# zeta2rework_lw_v15.net
KiCad netlist of a schematic drawn in EAGLE
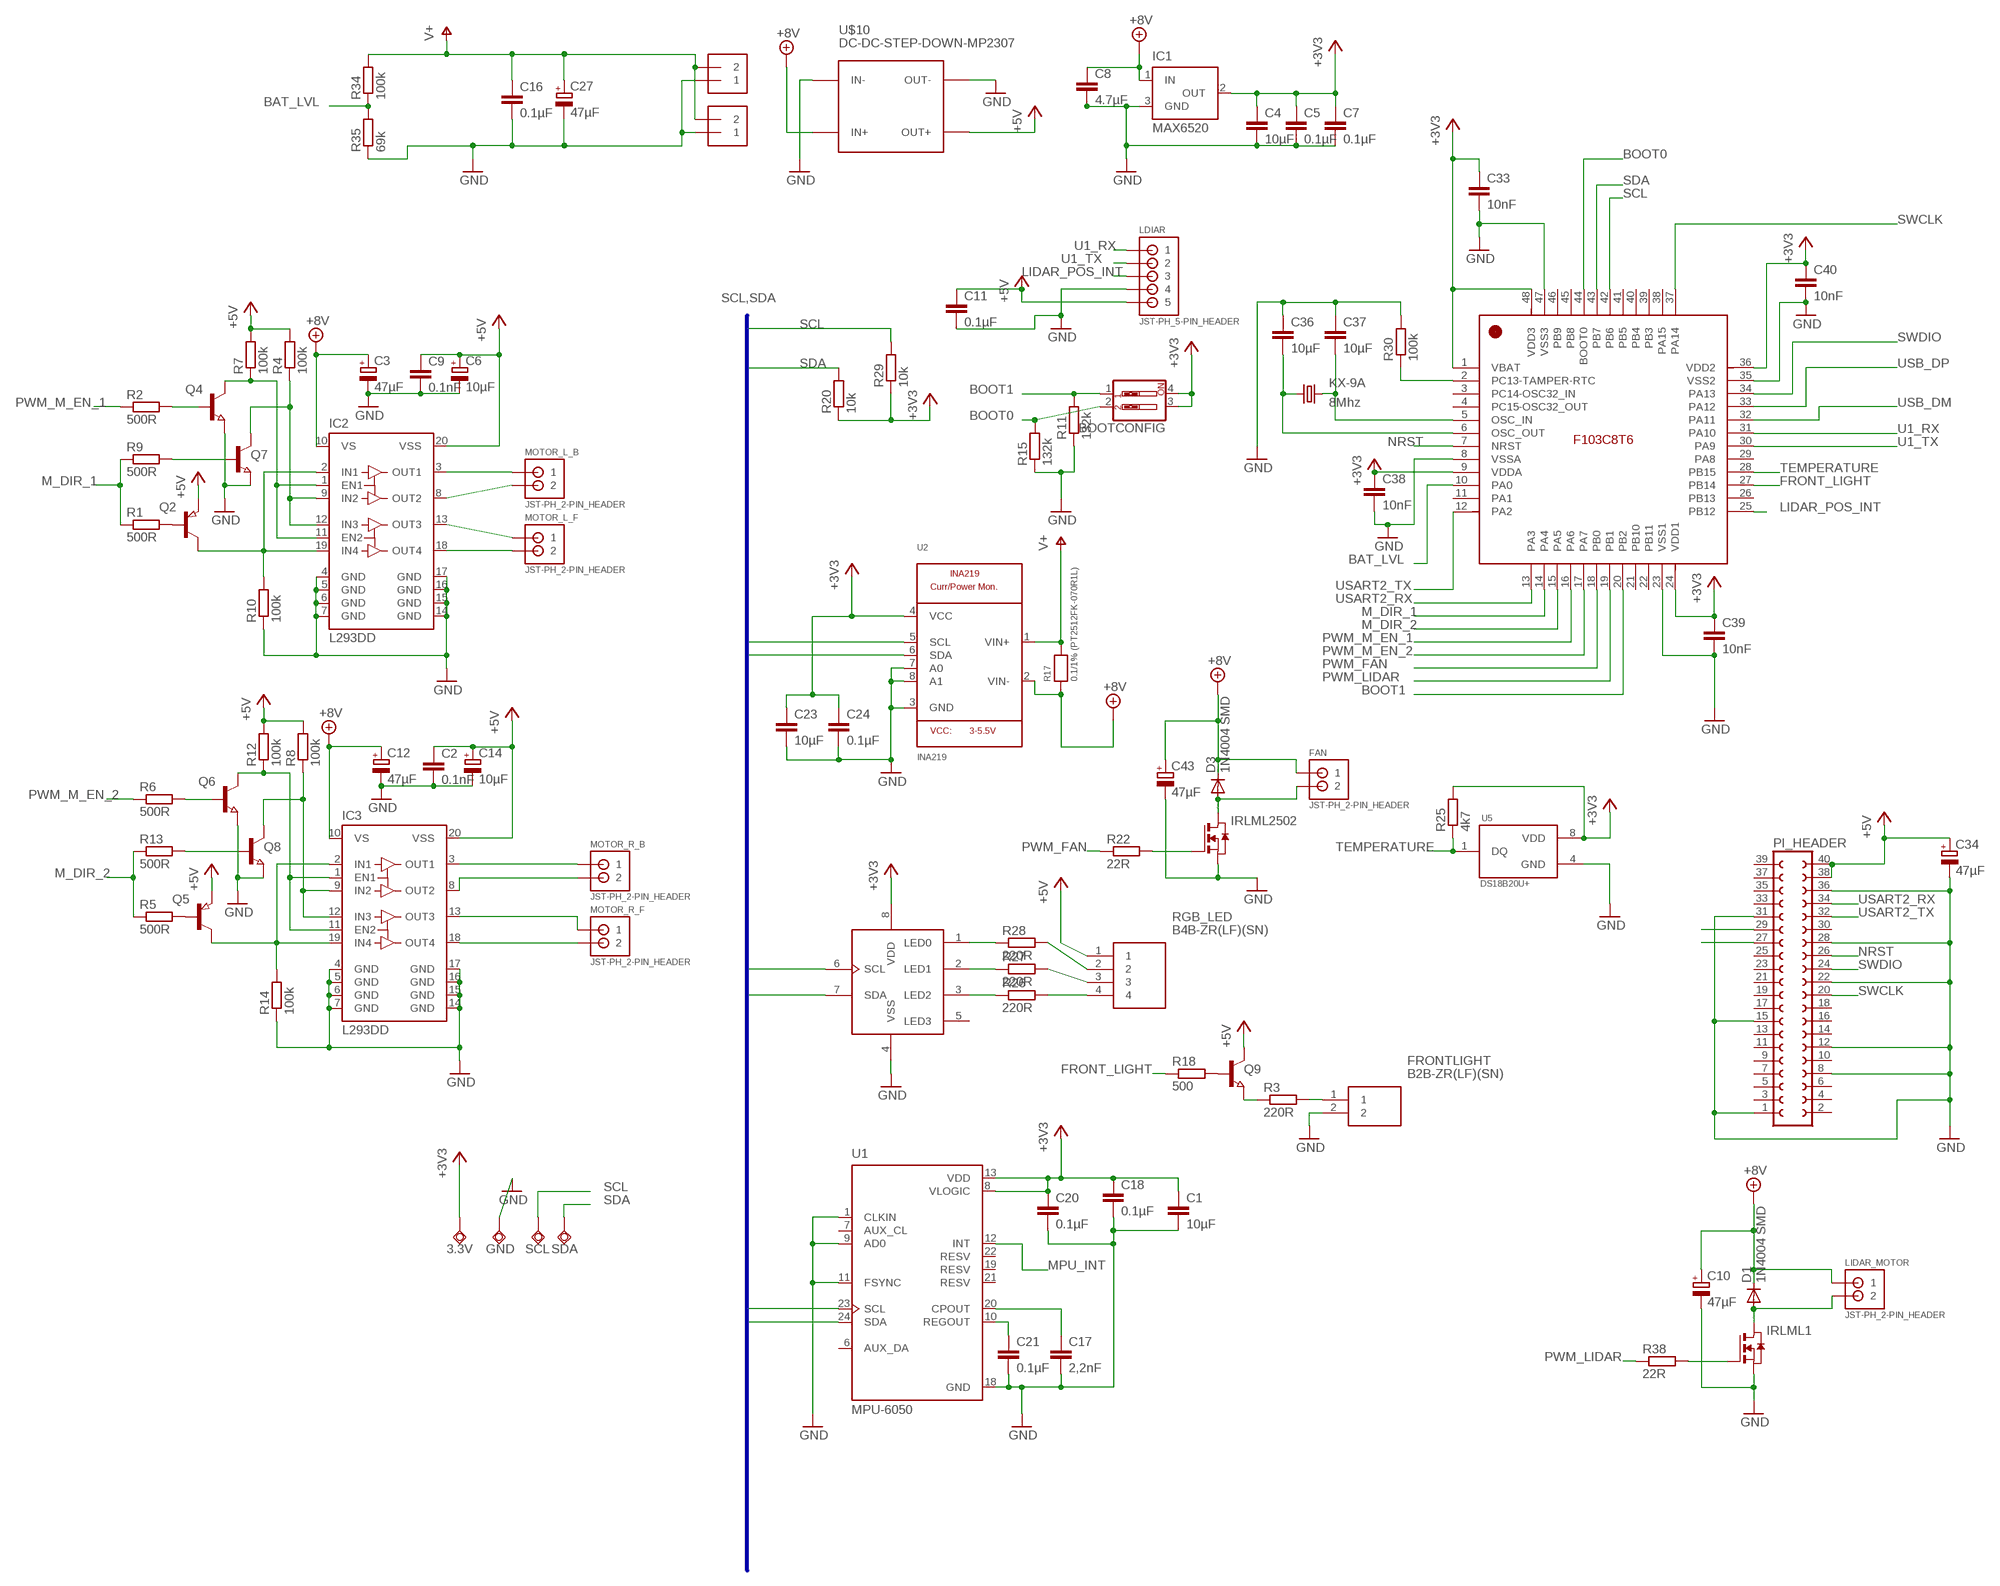
[diagram p0: schematic, sheet 1]

(export (version "E")
  (design (tool "Eeschema 10.0.6"))
  (components
    (comp (ref "3.3V")
      (value "TPSQTP20R")
      (footprint "eagle-import:TP20R")
      (libsource (lib "eagle-import") (part "TPSQTP20R"))
    )
    (comp (ref "BOOTCONFIG")
      (value "SW_DIP-2")
      (footprint "eagle-import:EDG-02")
      (libsource (lib "eagle-import") (part "SW_DIP-2"))
    )
    (comp (ref "C1")
      (value "10µF")
      (footprint "eagle-import:C1206")
      (libsource (lib "eagle-import") (part "C-EUC1206"))
    )
    (comp (ref "C2")
      (value "0.1nF")
      (footprint "eagle-import:C1206")
      (libsource (lib "eagle-import") (part "C-EUC1206"))
    )
    (comp (ref "C3")
      (value "47µF")
      (footprint "eagle-import:UD-4X5,8_NICHICON")
      (libsource (lib "eagle-import") (part "CPOL-EUUD-4X5,8"))
    )
    (comp (ref "C4")
      (value "10µF")
      (footprint "eagle-import:C1206")
      (libsource (lib "eagle-import") (part "C-EUC1206"))
    )
    (comp (ref "C5")
      (value "0.1µF")
      (footprint "eagle-import:C1206")
      (libsource (lib "eagle-import") (part "C-EUC1206"))
    )
    (comp (ref "C6")
      (value "10µF")
      (footprint "eagle-import:UD-4X5,8_NICHICON")
      (libsource (lib "eagle-import") (part "CPOL-EUUD-4X5,8"))
    )
    (comp (ref "C7")
      (value "0.1µF")
      (footprint "eagle-import:C1206")
      (libsource (lib "eagle-import") (part "C-EUC1206"))
    )
    (comp (ref "C8")
      (value "4.7µF")
      (footprint "eagle-import:C1206")
      (libsource (lib "eagle-import") (part "C-EUC1206"))
    )
    (comp (ref "C9")
      (value "0.1nF")
      (footprint "eagle-import:C1206")
      (libsource (lib "eagle-import") (part "C-EUC1206"))
    )
    (comp (ref "C10")
      (value "47µF")
      (footprint "eagle-import:UD-4X5,8_NICHICON")
      (libsource (lib "eagle-import") (part "CPOL-EUUD-4X5,8"))
    )
    (comp (ref "C11")
      (value "0.1µF")
      (footprint "eagle-import:C1206")
      (libsource (lib "eagle-import") (part "C-EUC1206"))
    )
    (comp (ref "C12")
      (value "47µF")
      (footprint "eagle-import:UD-4X5,8_NICHICON")
      (libsource (lib "eagle-import") (part "CPOL-EUUD-4X5,8"))
    )
    (comp (ref "C14")
      (value "10µF")
      (footprint "eagle-import:UD-4X5,8_NICHICON")
      (libsource (lib "eagle-import") (part "CPOL-EUUD-4X5,8"))
    )
    (comp (ref "C16")
      (value "0.1µF")
      (footprint "eagle-import:C1206")
      (libsource (lib "eagle-import") (part "C-EUC1206"))
    )
    (comp (ref "C17")
      (value "2,2nF")
      (footprint "eagle-import:C1206")
      (libsource (lib "eagle-import") (part "C-EUC1206"))
    )
    (comp (ref "C18")
      (value "0.1µF")
      (footprint "eagle-import:C1206")
      (libsource (lib "eagle-import") (part "C-EUC1206"))
    )
    (comp (ref "C20")
      (value "0.1µF")
      (footprint "eagle-import:C1206")
      (libsource (lib "eagle-import") (part "C-EUC1206"))
    )
    (comp (ref "C21")
      (value "0.1µF")
      (footprint "eagle-import:C1206")
      (libsource (lib "eagle-import") (part "C-EUC1206"))
    )
    (comp (ref "C23")
      (value "10µF")
      (footprint "eagle-import:C1206")
      (libsource (lib "eagle-import") (part "C-EUC1206"))
    )
    (comp (ref "C24")
      (value "0.1µF")
      (footprint "eagle-import:C1206")
      (libsource (lib "eagle-import") (part "C-EUC1206"))
    )
    (comp (ref "C27")
      (value "47µF")
      (footprint "eagle-import:UD-4X5,8_NICHICON")
      (libsource (lib "eagle-import") (part "CPOL-EUUD-4X5,8"))
    )
    (comp (ref "C33")
      (value "10nF")
      (footprint "eagle-import:C1206")
      (libsource (lib "eagle-import") (part "C-EUC1206"))
    )
    (comp (ref "C34")
      (value "47µF")
      (footprint "eagle-import:UD-4X5,8_NICHICON")
      (libsource (lib "eagle-import") (part "CPOL-EUUD-4X5,8"))
    )
    (comp (ref "C36")
      (value "10µF")
      (footprint "eagle-import:C1206")
      (libsource (lib "eagle-import") (part "C-EUC1206"))
    )
    (comp (ref "C37")
      (value "10µF")
      (footprint "eagle-import:C1206")
      (libsource (lib "eagle-import") (part "C-EUC1206"))
    )
    (comp (ref "C38")
      (value "10nF")
      (footprint "eagle-import:C1206")
      (libsource (lib "eagle-import") (part "C-EUC1206"))
    )
    (comp (ref "C39")
      (value "10nF")
      (footprint "eagle-import:C1206")
      (libsource (lib "eagle-import") (part "C-EUC1206"))
    )
    (comp (ref "C40")
      (value "10nF")
      (footprint "eagle-import:C1206")
      (libsource (lib "eagle-import") (part "C-EUC1206"))
    )
    (comp (ref "C43")
      (value "47µF")
      (footprint "eagle-import:UD-4X5,8_NICHICON")
      (libsource (lib "eagle-import") (part "CPOL-EUUD-4X5,8"))
    )
    (comp (ref "D1")
      (value "1N4004 SMD")
      (footprint "eagle-import:DO214AC")
      (libsource (lib "eagle-import") (part "DIODE-DO214AC"))
    )
    (comp (ref "D3")
      (value "1N4004 SMD")
      (footprint "eagle-import:DO214AC")
      (libsource (lib "eagle-import") (part "DIODE-DO214AC"))
    )
    (comp (ref "FAN")
      (value "JST-PH_2-PIN_HEADER")
      (footprint "eagle-import:JST_B2B-PH_HEADER")
      (libsource (lib "eagle-import") (part "JST-PH_2-PIN_HEADER"))
    )
    (comp (ref "FRONTLIGHT")
      (value "B2B-ZR(LF)(SN)")
      (footprint "eagle-import:SHDR2W50P0X150_1X2_450X350X450")
      (fields (field (name "MOUSER_PART_NUMBER") "1724868"))
      (libsource (lib "eagle-import") (part "B2B-ZR(LF)(SN)"))
    )
    (comp (ref "GND")
      (value "TPSQTP20R")
      (footprint "eagle-import:TP20R")
      (libsource (lib "eagle-import") (part "TPSQTP20R"))
    )
    (comp (ref "IC1")
      (value "MAX6520")
      (footprint "eagle-import:SOT23")
      (fields (field (name "MF") "MAXIM") (field (name "MPN") "MAX6520EUR-T"))
      (libsource (lib "eagle-import") (part "MAX6520"))
    )
    (comp (ref "IC2")
      (value "L293DD")
      (footprint "eagle-import:SO20")
      (libsource (lib "eagle-import") (part "L293DD"))
    )
    (comp (ref "IC3")
      (value "L293DD")
      (footprint "eagle-import:SO20")
      (libsource (lib "eagle-import") (part "L293DD"))
    )
    (comp (ref "IRLML1")
      (value "NMOSSOT23")
      (footprint "eagle-import:SOT-23")
      (libsource (lib "eagle-import") (part "NMOSSOT23"))
    )
    (comp (ref "IRLML2502")
      (value "NMOSSOT23")
      (footprint "eagle-import:SOT-23")
      (libsource (lib "eagle-import") (part "NMOSSOT23"))
    )
    (comp (ref "KX-9A")
      (value "8Mhz")
      (footprint "eagle-import:5.0X3.2_KX-9A")
      (libsource (lib "eagle-import") (part "KX-9A"))
    )
    (comp (ref "LDIAR")
      (value "JST-PH_5-PIN_HEADER")
      (footprint "eagle-import:JST_B5B-PH_HEADER")
      (libsource (lib "eagle-import") (part "JST-PH_5-PIN_HEADER"))
    )
    (comp (ref "LIDAR_MOTOR")
      (value "JST-PH_2-PIN_HEADER")
      (footprint "eagle-import:JST_B2B-PH_HEADER")
      (libsource (lib "eagle-import") (part "JST-PH_2-PIN_HEADER"))
    )
    (comp (ref "MOTOR_L_B")
      (value "JST-PH_2-PIN_HEADER")
      (footprint "eagle-import:JST_B2B-PH_HEADER")
      (libsource (lib "eagle-import") (part "JST-PH_2-PIN_HEADER"))
    )
    (comp (ref "MOTOR_L_F")
      (value "JST-PH_2-PIN_HEADER")
      (footprint "eagle-import:JST_B2B-PH_HEADER")
      (libsource (lib "eagle-import") (part "JST-PH_2-PIN_HEADER"))
    )
    (comp (ref "MOTOR_R_B")
      (value "JST-PH_2-PIN_HEADER")
      (footprint "eagle-import:JST_B2B-PH_HEADER")
      (libsource (lib "eagle-import") (part "JST-PH_2-PIN_HEADER"))
    )
    (comp (ref "MOTOR_R_F")
      (value "JST-PH_2-PIN_HEADER")
      (footprint "eagle-import:JST_B2B-PH_HEADER")
      (libsource (lib "eagle-import") (part "JST-PH_2-PIN_HEADER"))
    )
    (comp (ref "PCA9533")
      (value "PCA9533")
      (footprint "eagle-import:SOIC8")
      (libsource (lib "eagle-import") (part "PCA9533"))
    )
    (comp (ref "PI_HEADER")
      (value "FE20-2")
      (footprint "eagle-import:FE20-2")
      (libsource (lib "eagle-import") (part "FE20-2"))
    )
    (comp (ref "Q2")
      (value "PNP-TRANSISTOR_SOT23")
      (footprint "eagle-import:SOT23")
      (libsource (lib "eagle-import") (part "PNP-TRANSISTOR_SOT23"))
    )
    (comp (ref "Q4")
      (value "NPN-TRANSISTOR_SOT23")
      (footprint "eagle-import:SOT23")
      (libsource (lib "eagle-import") (part "NPN-TRANSISTOR_SOT23"))
    )
    (comp (ref "Q5")
      (value "PNP-TRANSISTOR_SOT23")
      (footprint "eagle-import:SOT23")
      (libsource (lib "eagle-import") (part "PNP-TRANSISTOR_SOT23"))
    )
    (comp (ref "Q6")
      (value "NPN-TRANSISTOR_SOT23")
      (footprint "eagle-import:SOT23")
      (libsource (lib "eagle-import") (part "NPN-TRANSISTOR_SOT23"))
    )
    (comp (ref "Q7")
      (value "NPN-TRANSISTOR_SOT23")
      (footprint "eagle-import:SOT23")
      (libsource (lib "eagle-import") (part "NPN-TRANSISTOR_SOT23"))
    )
    (comp (ref "Q8")
      (value "NPN-TRANSISTOR_SOT23")
      (footprint "eagle-import:SOT23")
      (libsource (lib "eagle-import") (part "NPN-TRANSISTOR_SOT23"))
    )
    (comp (ref "Q9")
      (value "NPN-TRANSISTOR_SOT23")
      (footprint "eagle-import:SOT23")
      (libsource (lib "eagle-import") (part "NPN-TRANSISTOR_SOT23"))
    )
    (comp (ref "R1")
      (value "500R")
      (footprint "eagle-import:R0603")
      (libsource (lib "eagle-import") (part "R-EU_R0603"))
    )
    (comp (ref "R2")
      (value "500R")
      (footprint "eagle-import:R0603")
      (libsource (lib "eagle-import") (part "R-EU_R0603"))
    )
    (comp (ref "R3")
      (value "220R")
      (footprint "eagle-import:R0603")
      (libsource (lib "eagle-import") (part "R-EU_R0603"))
    )
    (comp (ref "R4")
      (value "100k")
      (footprint "eagle-import:R0603")
      (libsource (lib "eagle-import") (part "R-EU_R0603"))
    )
    (comp (ref "R5")
      (value "500R")
      (footprint "eagle-import:R0603")
      (libsource (lib "eagle-import") (part "R-EU_R0603"))
    )
    (comp (ref "R6")
      (value "500R")
      (footprint "eagle-import:R0603")
      (libsource (lib "eagle-import") (part "R-EU_R0603"))
    )
    (comp (ref "R7")
      (value "100k")
      (footprint "eagle-import:R0603")
      (libsource (lib "eagle-import") (part "R-EU_R0603"))
    )
    (comp (ref "R8")
      (value "100k")
      (footprint "eagle-import:R0603")
      (libsource (lib "eagle-import") (part "R-EU_R0603"))
    )
    (comp (ref "R9")
      (value "500R")
      (footprint "eagle-import:R0603")
      (libsource (lib "eagle-import") (part "R-EU_R0603"))
    )
    (comp (ref "R10")
      (value "100k")
      (footprint "eagle-import:R0603")
      (libsource (lib "eagle-import") (part "R-EU_R0603"))
    )
    (comp (ref "R11")
      (value "132k")
      (footprint "eagle-import:R0603")
      (libsource (lib "eagle-import") (part "R-EU_R0603"))
    )
    (comp (ref "R12")
      (value "100k")
      (footprint "eagle-import:R0603")
      (libsource (lib "eagle-import") (part "R-EU_R0603"))
    )
    (comp (ref "R13")
      (value "500R")
      (footprint "eagle-import:R0603")
      (libsource (lib "eagle-import") (part "R-EU_R0603"))
    )
    (comp (ref "R14")
      (value "100k")
      (footprint "eagle-import:R0603")
      (libsource (lib "eagle-import") (part "R-EU_R0603"))
    )
    (comp (ref "R15")
      (value "132k")
      (footprint "eagle-import:R0603")
      (libsource (lib "eagle-import") (part "R-EU_R0603"))
    )
    (comp (ref "R17")
      (value "0.1/1% (PT2512FK-070R1L)")
      (footprint "eagle-import:2512")
      (libsource (lib "eagle-import") (part "RESISTOR2512"))
    )
    (comp (ref "R18")
      (value "500")
      (footprint "eagle-import:R1206")
      (libsource (lib "eagle-import") (part "R-EU_R1206"))
    )
    (comp (ref "R20")
      (value "10k")
      (footprint "eagle-import:R0603")
      (libsource (lib "eagle-import") (part "R-EU_R0603"))
    )
    (comp (ref "R22")
      (value "22R")
      (footprint "eagle-import:R0603")
      (libsource (lib "eagle-import") (part "R-EU_R0603"))
    )
    (comp (ref "R25")
      (value "4k7")
      (footprint "eagle-import:R0603")
      (libsource (lib "eagle-import") (part "R-EU_R0603"))
    )
    (comp (ref "R26")
      (value "220R")
      (footprint "eagle-import:R0603")
      (libsource (lib "eagle-import") (part "R-EU_R0603"))
    )
    (comp (ref "R27")
      (value "220R")
      (footprint "eagle-import:R0603")
      (libsource (lib "eagle-import") (part "R-EU_R0603"))
    )
    (comp (ref "R28")
      (value "220R")
      (footprint "eagle-import:R0603")
      (libsource (lib "eagle-import") (part "R-EU_R0603"))
    )
    (comp (ref "R29")
      (value "10k")
      (footprint "eagle-import:R0603")
      (libsource (lib "eagle-import") (part "R-EU_R0603"))
    )
    (comp (ref "R30")
      (value "100k")
      (footprint "eagle-import:R0603")
      (libsource (lib "eagle-import") (part "R-EU_R0603"))
    )
    (comp (ref "R34")
      (value "100k")
      (footprint "eagle-import:R0603")
      (libsource (lib "eagle-import") (part "R-EU_R0603"))
    )
    (comp (ref "R35")
      (value "69k")
      (footprint "eagle-import:R0603")
      (libsource (lib "eagle-import") (part "R-EU_R0603"))
    )
    (comp (ref "R38")
      (value "22R")
      (footprint "eagle-import:R0603")
      (libsource (lib "eagle-import") (part "R-EU_R0603"))
    )
    (comp (ref "RGB_LED")
      (value "B4B-ZR(LF)(SN)")
      (footprint "eagle-import:SHDR4W50P0X150_1X4_750X350X450")
      (fields (field (name "FARNELL_PART_NUMBER") "9491791"))
      (libsource (lib "eagle-import") (part "B4B-ZR(LF)(SN)"))
    )
    (comp (ref "SCL")
      (value "TPSQTP20R")
      (footprint "eagle-import:TP20R")
      (libsource (lib "eagle-import") (part "TPSQTP20R"))
    )
    (comp (ref "SDA")
      (value "TPSQTP20R")
      (footprint "eagle-import:TP20R")
      (libsource (lib "eagle-import") (part "TPSQTP20R"))
    )
    (comp (ref "STM32F103CB")
      (value "STM32F103CB")
      (footprint "eagle-import:LQFP48_7X7MM_0.5MMPP")
      (fields (field (name "MF") "STMicroelectronics") (field (name "MP") "STM32F103C8T6"))
      (libsource (lib "eagle-import") (part "STM32F103C8T6"))
    )
    (comp (ref "SUPPLY_IN")
      (value "TERMBLOCK_1X2-3.5MM")
      (footprint "eagle-import:1X2-3.5MM")
      (libsource (lib "eagle-import") (part "TERMBLOCK_1X2-3.5MM"))
    )
    (comp (ref "SUPPLY_IN1")
      (value "TERMBLOCK_1X2-3.5MM")
      (footprint "eagle-import:1X2-3.5MM")
      (libsource (lib "eagle-import") (part "TERMBLOCK_1X2-3.5MM"))
    )
    (comp (ref "U$10")
      (value "DC-DC-STEP-DOWN-MP2307")
      (footprint "eagle-import:DC-DC-STEP-DOWN-MP2307")
      (libsource (lib "eagle-import") (part "DC-DC-STEP-DOWN-MP2307"))
    )
    (comp (ref "U1")
      (value "MPU-6050")
      (footprint "eagle-import:QFN50P400X400X95-24N")
      (fields (field (name "MF") "TDK"))
      (libsource (lib "eagle-import") (part "MPU-6050"))
    )
    (comp (ref "U2")
      (value "INA219")
      (footprint "eagle-import:SOT23-8")
      (fields (field (name "MF") "Texas Instruments"))
      (libsource (lib "eagle-import") (part "INA219"))
    )
    (comp (ref "U5")
      (value "DS18B20U+")
      (footprint "eagle-import:SOP65P490X95-8N")
      (fields (field (name "MF") "Maxim"))
      (libsource (lib "eagle-import") (part "DS18B20U+"))
    )
  )
  (nets
    (net (code "1") (name "+3V3") (class "Default")
      (node (ref "3.3V") (pin "TP") (pinfunction "TP_TP") (pintype "input"))
      (node (ref "BOOTCONFIG") (pin "3") (pinfunction "3_3") (pintype "passive"))
      (node (ref "BOOTCONFIG") (pin "4") (pinfunction "4_4") (pintype "passive"))
      (node (ref "C1") (pin "1") (pinfunction "1_1") (pintype "passive"))
      (node (ref "C18") (pin "1") (pinfunction "1_1") (pintype "passive"))
      (node (ref "C20") (pin "1") (pinfunction "1_1") (pintype "passive"))
      (node (ref "C23") (pin "1") (pinfunction "1_1") (pintype "passive"))
      (node (ref "C24") (pin "1") (pinfunction "1_1") (pintype "passive"))
      (node (ref "C33") (pin "1") (pinfunction "1_1") (pintype "passive"))
      (node (ref "C38") (pin "1") (pinfunction "1_1") (pintype "passive"))
      (node (ref "C39") (pin "1") (pinfunction "1_1") (pintype "passive"))
      (node (ref "C4") (pin "1") (pinfunction "1_1") (pintype "passive"))
      (node (ref "C40") (pin "1") (pinfunction "1_1") (pintype "passive"))
      (node (ref "C5") (pin "1") (pinfunction "1_1") (pintype "passive"))
      (node (ref "C7") (pin "1") (pinfunction "1_1") (pintype "passive"))
      (node (ref "IC1") (pin "2") (pinfunction "OUT_2") (pintype "output"))
      (node (ref "PCA9533") (pin "8") (pinfunction "VDD_8") (pintype "power_in"))
      (node (ref "R20") (pin "1") (pinfunction "1_1") (pintype "passive"))
      (node (ref "R25") (pin "2") (pinfunction "2_2") (pintype "passive"))
      (node (ref "R29") (pin "1") (pinfunction "1_1") (pintype "passive"))
      (node (ref "STM32F103CB") (pin "1") (pinfunction "VBAT_1") (pintype "bidirectional"))
      (node (ref "STM32F103CB") (pin "24") (pinfunction "VDD1_24") (pintype "bidirectional"))
      (node (ref "STM32F103CB") (pin "36") (pinfunction "VDD2_36") (pintype "bidirectional"))
      (node (ref "STM32F103CB") (pin "48") (pinfunction "VDD3_48") (pintype "bidirectional"))
      (node (ref "STM32F103CB") (pin "9") (pinfunction "VDDA_9") (pintype "bidirectional"))
      (node (ref "U1") (pin "13") (pinfunction "VDD_13") (pintype "power_in"))
      (node (ref "U1") (pin "8") (pinfunction "VLOGIC_8") (pintype "power_in"))
      (node (ref "U2") (pin "4") (pinfunction "VCC_4") (pintype "bidirectional"))
      (node (ref "U5") (pin "8") (pinfunction "VDD_8") (pintype "power_in"))
    )
    (net (code "2") (name "+5V") (class "Default")
      (node (ref "C11") (pin "1") (pinfunction "1_1") (pintype "passive"))
      (node (ref "C14") (pin "+") (pinfunction "+_+") (pintype "passive"))
      (node (ref "C2") (pin "1") (pinfunction "1_1") (pintype "passive"))
      (node (ref "C34") (pin "+") (pinfunction "+_+") (pintype "passive"))
      (node (ref "C6") (pin "+") (pinfunction "+_+") (pintype "passive"))
      (node (ref "C9") (pin "1") (pinfunction "1_1") (pintype "passive"))
      (node (ref "IC2") (pin "20") (pinfunction "VSS_20") (pintype "power_in"))
      (node (ref "IC3") (pin "20") (pinfunction "VSS_20") (pintype "power_in"))
      (node (ref "LDIAR") (pin "P5") (pinfunction "5_P5") (pintype "bidirectional"))
      (node (ref "PI_HEADER") (pin "38") (pinfunction "38_38") (pintype "passive"))
      (node (ref "PI_HEADER") (pin "40") (pinfunction "40_40") (pintype "passive"))
      (node (ref "Q2") (pin "2") (pinfunction "E_2") (pintype "passive"))
      (node (ref "Q5") (pin "2") (pinfunction "E_2") (pintype "passive"))
      (node (ref "Q9") (pin "3") (pinfunction "C_3") (pintype "passive"))
      (node (ref "R12") (pin "2") (pinfunction "2_2") (pintype "passive"))
      (node (ref "R4") (pin "2") (pinfunction "2_2") (pintype "passive"))
      (node (ref "R7") (pin "2") (pinfunction "2_2") (pintype "passive"))
      (node (ref "R8") (pin "2") (pinfunction "2_2") (pintype "passive"))
      (node (ref "RGB_LED") (pin "1") (pinfunction "1_1") (pintype "bidirectional"))
      (node (ref "U$10") (pin "OUT+") (pinfunction "OUT+_OUT+") (pintype "bidirectional"))
    )
    (net (code "3") (name "+8V") (class "Default")
      (node (ref "C10") (pin "+") (pinfunction "+_+") (pintype "passive"))
      (node (ref "C12") (pin "+") (pinfunction "+_+") (pintype "passive"))
      (node (ref "C3") (pin "+") (pinfunction "+_+") (pintype "passive"))
      (node (ref "C43") (pin "+") (pinfunction "+_+") (pintype "passive"))
      (node (ref "C8") (pin "1") (pinfunction "1_1") (pintype "passive"))
      (node (ref "D1") (pin "C") (pinfunction "C_C") (pintype "passive"))
      (node (ref "D3") (pin "C") (pinfunction "C_C") (pintype "passive"))
      (node (ref "FAN") (pin "P1") (pinfunction "1_P1") (pintype "bidirectional"))
      (node (ref "IC1") (pin "1") (pinfunction "IN_1") (pintype "input"))
      (node (ref "IC2") (pin "10") (pinfunction "VS_10") (pintype "power_in"))
      (node (ref "IC3") (pin "10") (pinfunction "VS_10") (pintype "power_in"))
      (node (ref "LIDAR_MOTOR") (pin "P1") (pinfunction "1_P1") (pintype "bidirectional"))
      (node (ref "R17") (pin "1") (pinfunction "1_1") (pintype "passive"))
      (node (ref "U$10") (pin "IN+") (pinfunction "IN+_IN+") (pintype "bidirectional"))
      (node (ref "U2") (pin "2") (pinfunction "VIN-_2") (pintype "bidirectional"))
    )
    (net (code "4") (name "/BAT_LVL") (class "Default")
      (node (ref "R34") (pin "1") (pinfunction "1_1") (pintype "passive"))
      (node (ref "R35") (pin "2") (pinfunction "2_2") (pintype "passive"))
      (node (ref "STM32F103CB") (pin "10") (pinfunction "PA0_10") (pintype "bidirectional"))
    )
    (net (code "5") (name "/BOOT0") (class "Default")
      (node (ref "BOOTCONFIG") (pin "2") (pinfunction "2_2") (pintype "passive"))
      (node (ref "R15") (pin "2") (pinfunction "2_2") (pintype "passive"))
      (node (ref "STM32F103CB") (pin "44") (pinfunction "BOOT0_44") (pintype "bidirectional"))
    )
    (net (code "6") (name "/BOOT1") (class "Default")
      (node (ref "BOOTCONFIG") (pin "1") (pinfunction "1_1") (pintype "passive"))
      (node (ref "R11") (pin "2") (pinfunction "2_2") (pintype "passive"))
      (node (ref "STM32F103CB") (pin "20") (pinfunction "PB2_20") (pintype "bidirectional"))
    )
    (net (code "7") (name "/FRONT_LIGHT") (class "Default")
      (node (ref "R18") (pin "1") (pinfunction "1_1") (pintype "passive"))
      (node (ref "STM32F103CB") (pin "27") (pinfunction "PB14_27") (pintype "bidirectional"))
    )
    (net (code "8") (name "/LIDAR_POS_INT") (class "Default")
      (node (ref "LDIAR") (pin "P3") (pinfunction "3_P3") (pintype "bidirectional"))
      (node (ref "STM32F103CB") (pin "25") (pinfunction "PB12_25") (pintype "bidirectional"))
    )
    (net (code "9") (name "/MPU_INT") (class "Default")
      (node (ref "U1") (pin "12") (pinfunction "INT_12") (pintype "output"))
    )
    (net (code "10") (name "/M_DIR_1") (class "Default")
      (node (ref "R1") (pin "1") (pinfunction "1_1") (pintype "passive"))
      (node (ref "R9") (pin "1") (pinfunction "1_1") (pintype "passive"))
      (node (ref "STM32F103CB") (pin "14") (pinfunction "PA4_14") (pintype "bidirectional"))
    )
    (net (code "11") (name "/M_DIR_2") (class "Default")
      (node (ref "R13") (pin "1") (pinfunction "1_1") (pintype "passive"))
      (node (ref "R5") (pin "1") (pinfunction "1_1") (pintype "passive"))
      (node (ref "STM32F103CB") (pin "15") (pinfunction "PA5_15") (pintype "bidirectional"))
    )
    (net (code "12") (name "/NRST") (class "Default")
      (node (ref "PI_HEADER") (pin "26") (pinfunction "26_26") (pintype "passive"))
      (node (ref "STM32F103CB") (pin "7") (pinfunction "NRST_7") (pintype "bidirectional"))
    )
    (net (code "13") (name "/PWM_FAN") (class "Default")
      (node (ref "R22") (pin "1") (pinfunction "1_1") (pintype "passive"))
      (node (ref "STM32F103CB") (pin "18") (pinfunction "PB0_18") (pintype "bidirectional"))
    )
    (net (code "14") (name "/PWM_LIDAR") (class "Default")
      (node (ref "R38") (pin "1") (pinfunction "1_1") (pintype "passive"))
      (node (ref "STM32F103CB") (pin "19") (pinfunction "PB1_19") (pintype "bidirectional"))
    )
    (net (code "15") (name "/PWM_M_EN_1") (class "Default")
      (node (ref "R2") (pin "1") (pinfunction "1_1") (pintype "passive"))
      (node (ref "STM32F103CB") (pin "16") (pinfunction "PA6_16") (pintype "bidirectional"))
    )
    (net (code "16") (name "/PWM_M_EN_2") (class "Default")
      (node (ref "R6") (pin "1") (pinfunction "1_1") (pintype "passive"))
      (node (ref "STM32F103CB") (pin "17") (pinfunction "PA7_17") (pintype "bidirectional"))
    )
    (net (code "17") (name "/SCL") (class "Default")
      (node (ref "PCA9533") (pin "6") (pinfunction "SCL_6") (pintype "input"))
      (node (ref "R29") (pin "2") (pinfunction "2_2") (pintype "passive"))
      (node (ref "SCL") (pin "TP") (pinfunction "TP_TP") (pintype "input"))
      (node (ref "STM32F103CB") (pin "42") (pinfunction "PB6_42") (pintype "bidirectional"))
      (node (ref "U1") (pin "23") (pinfunction "SCL_23") (pintype "input"))
      (node (ref "U2") (pin "5") (pinfunction "SCL_5") (pintype "bidirectional"))
    )
    (net (code "18") (name "/SDA") (class "Default")
      (node (ref "PCA9533") (pin "7") (pinfunction "SDA_7") (pintype "bidirectional"))
      (node (ref "R20") (pin "2") (pinfunction "2_2") (pintype "passive"))
      (node (ref "SDA") (pin "TP") (pinfunction "TP_TP") (pintype "input"))
      (node (ref "STM32F103CB") (pin "43") (pinfunction "PB7_43") (pintype "bidirectional"))
      (node (ref "U1") (pin "24") (pinfunction "SDA_24") (pintype "bidirectional"))
      (node (ref "U2") (pin "6") (pinfunction "SDA_6") (pintype "bidirectional"))
    )
    (net (code "19") (name "/SWCLK") (class "Default")
      (node (ref "PI_HEADER") (pin "20") (pinfunction "20_20") (pintype "passive"))
      (node (ref "STM32F103CB") (pin "37") (pinfunction "PA14_37") (pintype "bidirectional"))
    )
    (net (code "20") (name "/SWDIO") (class "Default")
      (node (ref "PI_HEADER") (pin "24") (pinfunction "24_24") (pintype "passive"))
      (node (ref "STM32F103CB") (pin "34") (pinfunction "PA13_34") (pintype "bidirectional"))
    )
    (net (code "21") (name "/TEMPERATURE") (class "Default")
      (node (ref "R25") (pin "1") (pinfunction "1_1") (pintype "passive"))
      (node (ref "STM32F103CB") (pin "28") (pinfunction "PB15_28") (pintype "bidirectional"))
      (node (ref "U5") (pin "1") (pinfunction "DQ_1") (pintype "bidirectional"))
    )
    (net (code "22") (name "/U1_RX") (class "Default")
      (node (ref "LDIAR") (pin "P1") (pinfunction "1_P1") (pintype "bidirectional"))
      (node (ref "STM32F103CB") (pin "31") (pinfunction "PA10_31") (pintype "bidirectional"))
    )
    (net (code "23") (name "/U1_TX") (class "Default")
      (node (ref "LDIAR") (pin "P2") (pinfunction "2_P2") (pintype "bidirectional"))
      (node (ref "STM32F103CB") (pin "30") (pinfunction "PA9_30") (pintype "bidirectional"))
    )
    (net (code "24") (name "/USART2_RX") (class "Default")
      (node (ref "PI_HEADER") (pin "34") (pinfunction "34_34") (pintype "passive"))
      (node (ref "STM32F103CB") (pin "13") (pinfunction "PA3_13") (pintype "bidirectional"))
    )
    (net (code "25") (name "/USART2_TX") (class "Default")
      (node (ref "PI_HEADER") (pin "32") (pinfunction "32_32") (pintype "passive"))
      (node (ref "STM32F103CB") (pin "12") (pinfunction "PA2_12") (pintype "bidirectional"))
    )
    (net (code "26") (name "/USB_DM") (class "Default")
      (node (ref "STM32F103CB") (pin "32") (pinfunction "PA11_32") (pintype "bidirectional"))
    )
    (net (code "27") (name "/USB_DP") (class "Default")
      (node (ref "STM32F103CB") (pin "33") (pinfunction "PA12_33") (pintype "bidirectional"))
    )
    (net (code "29") (name "GND") (class "Default")
      (node (ref "C1") (pin "2") (pinfunction "2_2") (pintype "passive"))
      (node (ref "C10") (pin "-") (pinfunction "-_-") (pintype "passive"))
      (node (ref "C11") (pin "2") (pinfunction "2_2") (pintype "passive"))
      (node (ref "C12") (pin "-") (pinfunction "-_-") (pintype "passive"))
      (node (ref "C14") (pin "-") (pinfunction "-_-") (pintype "passive"))
      (node (ref "C16") (pin "2") (pinfunction "2_2") (pintype "passive"))
      (node (ref "C17") (pin "2") (pinfunction "2_2") (pintype "passive"))
      (node (ref "C18") (pin "2") (pinfunction "2_2") (pintype "passive"))
      (node (ref "C2") (pin "2") (pinfunction "2_2") (pintype "passive"))
      (node (ref "C20") (pin "2") (pinfunction "2_2") (pintype "passive"))
      (node (ref "C21") (pin "2") (pinfunction "2_2") (pintype "passive"))
      (node (ref "C23") (pin "2") (pinfunction "2_2") (pintype "passive"))
      (node (ref "C24") (pin "2") (pinfunction "2_2") (pintype "passive"))
      (node (ref "C27") (pin "-") (pinfunction "-_-") (pintype "passive"))
      (node (ref "C3") (pin "-") (pinfunction "-_-") (pintype "passive"))
      (node (ref "C33") (pin "2") (pinfunction "2_2") (pintype "passive"))
      (node (ref "C34") (pin "-") (pinfunction "-_-") (pintype "passive"))
      (node (ref "C36") (pin "1") (pinfunction "1_1") (pintype "passive"))
      (node (ref "C37") (pin "1") (pinfunction "1_1") (pintype "passive"))
      (node (ref "C38") (pin "2") (pinfunction "2_2") (pintype "passive"))
      (node (ref "C39") (pin "2") (pinfunction "2_2") (pintype "passive"))
      (node (ref "C4") (pin "2") (pinfunction "2_2") (pintype "passive"))
      (node (ref "C40") (pin "2") (pinfunction "2_2") (pintype "passive"))
      (node (ref "C43") (pin "-") (pinfunction "-_-") (pintype "passive"))
      (node (ref "C5") (pin "2") (pinfunction "2_2") (pintype "passive"))
      (node (ref "C6") (pin "-") (pinfunction "-_-") (pintype "passive"))
      (node (ref "C7") (pin "2") (pinfunction "2_2") (pintype "passive"))
      (node (ref "C8") (pin "2") (pinfunction "2_2") (pintype "passive"))
      (node (ref "C9") (pin "2") (pinfunction "2_2") (pintype "passive"))
      (node (ref "FRONTLIGHT") (pin "2") (pinfunction "2_2") (pintype "bidirectional"))
      (node (ref "GND") (pin "TP") (pinfunction "TP_TP") (pintype "input"))
      (node (ref "IC1") (pin "3") (pinfunction "GND_3") (pintype "power_in"))
      (node (ref "IC2") (pin "14") (pinfunction "GND_14") (pintype "power_in"))
      (node (ref "IC2") (pin "15") (pinfunction "GND_15") (pintype "power_in"))
      (node (ref "IC2") (pin "16") (pinfunction "GND_16") (pintype "power_in"))
      (node (ref "IC2") (pin "17") (pinfunction "GND_17") (pintype "power_in"))
      (node (ref "IC2") (pin "4") (pinfunction "GND_4") (pintype "power_in"))
      (node (ref "IC2") (pin "5") (pinfunction "GND_5") (pintype "power_in"))
      (node (ref "IC2") (pin "6") (pinfunction "GND_6") (pintype "power_in"))
      (node (ref "IC2") (pin "7") (pinfunction "GND_7") (pintype "power_in"))
      (node (ref "IC3") (pin "14") (pinfunction "GND_14") (pintype "power_in"))
      (node (ref "IC3") (pin "15") (pinfunction "GND_15") (pintype "power_in"))
      (node (ref "IC3") (pin "16") (pinfunction "GND_16") (pintype "power_in"))
      (node (ref "IC3") (pin "17") (pinfunction "GND_17") (pintype "power_in"))
      (node (ref "IC3") (pin "4") (pinfunction "GND_4") (pintype "power_in"))
      (node (ref "IC3") (pin "5") (pinfunction "GND_5") (pintype "power_in"))
      (node (ref "IC3") (pin "6") (pinfunction "GND_6") (pintype "power_in"))
      (node (ref "IC3") (pin "7") (pinfunction "GND_7") (pintype "power_in"))
      (node (ref "IRLML1") (pin "2") (pinfunction "S_2") (pintype "passive"))
      (node (ref "IRLML2502") (pin "2") (pinfunction "S_2") (pintype "passive"))
      (node (ref "LDIAR") (pin "P4") (pinfunction "4_P4") (pintype "bidirectional"))
      (node (ref "PCA9533") (pin "4") (pinfunction "VSS_4") (pintype "power_in"))
      (node (ref "PI_HEADER") (pin "1") (pinfunction "1_1") (pintype "passive"))
      (node (ref "PI_HEADER") (pin "12") (pinfunction "12_12") (pintype "passive"))
      (node (ref "PI_HEADER") (pin "15") (pinfunction "15_15") (pintype "passive"))
      (node (ref "PI_HEADER") (pin "22") (pinfunction "22_22") (pintype "passive"))
      (node (ref "PI_HEADER") (pin "28") (pinfunction "28_28") (pintype "passive"))
      (node (ref "PI_HEADER") (pin "31") (pinfunction "31_31") (pintype "passive"))
      (node (ref "PI_HEADER") (pin "36") (pinfunction "36_36") (pintype "passive"))
      (node (ref "PI_HEADER") (pin "8") (pinfunction "8_8") (pintype "passive"))
      (node (ref "Q4") (pin "2") (pinfunction "E_2") (pintype "passive"))
      (node (ref "Q6") (pin "2") (pinfunction "E_2") (pintype "passive"))
      (node (ref "Q7") (pin "2") (pinfunction "E_2") (pintype "passive"))
      (node (ref "Q8") (pin "2") (pinfunction "E_2") (pintype "passive"))
      (node (ref "R10") (pin "1") (pinfunction "1_1") (pintype "passive"))
      (node (ref "R11") (pin "1") (pinfunction "1_1") (pintype "passive"))
      (node (ref "R14") (pin "1") (pinfunction "1_1") (pintype "passive"))
      (node (ref "R15") (pin "1") (pinfunction "1_1") (pintype "passive"))
      (node (ref "R30") (pin "2") (pinfunction "2_2") (pintype "passive"))
      (node (ref "R35") (pin "1") (pinfunction "1_1") (pintype "passive"))
      (node (ref "STM32F103CB") (pin "23") (pinfunction "VSS1_23") (pintype "bidirectional"))
      (node (ref "STM32F103CB") (pin "35") (pinfunction "VSS2_35") (pintype "bidirectional"))
      (node (ref "STM32F103CB") (pin "47") (pinfunction "VSS3_47") (pintype "bidirectional"))
      (node (ref "STM32F103CB") (pin "8") (pinfunction "VSSA_8") (pintype "bidirectional"))
      (node (ref "SUPPLY_IN") (pin "1") (pinfunction "1_1") (pintype "passive"))
      (node (ref "SUPPLY_IN1") (pin "1") (pinfunction "1_1") (pintype "passive"))
      (node (ref "U$10") (pin "IN-") (pinfunction "IN-_IN-") (pintype "bidirectional"))
      (node (ref "U$10") (pin "OUT-") (pinfunction "OUT-_OUT-") (pintype "bidirectional"))
      (node (ref "U1") (pin "1") (pinfunction "CLKIN_1") (pintype "input"))
      (node (ref "U1") (pin "11") (pinfunction "FSYNC_11") (pintype "input"))
      (node (ref "U1") (pin "18") (pinfunction "GND_18") (pintype "power_in"))
      (node (ref "U1") (pin "9") (pinfunction "AD0_9") (pintype "input"))
      (node (ref "U2") (pin "3") (pinfunction "GND_3") (pintype "bidirectional"))
      (node (ref "U2") (pin "7") (pinfunction "A0_7") (pintype "bidirectional"))
      (node (ref "U2") (pin "8") (pinfunction "A1_8") (pintype "bidirectional"))
      (node (ref "U5") (pin "4") (pinfunction "GND_4") (pintype "power_in"))
    )
    (net (code "30") (name "Net-(FAN-2)") (class "Default")
      (node (ref "D3") (pin "A") (pinfunction "A_A") (pintype "passive"))
      (node (ref "FAN") (pin "P2") (pinfunction "2_P2") (pintype "bidirectional"))
      (node (ref "IRLML2502") (pin "1") (pinfunction "D_1") (pintype "passive"))
    )
    (net (code "31") (name "Net-(FRONTLIGHT-Pad1)") (class "Default")
      (node (ref "FRONTLIGHT") (pin "1") (pinfunction "1_1") (pintype "bidirectional"))
      (node (ref "R3") (pin "2") (pinfunction "2_2") (pintype "passive"))
    )
    (net (code "32") (name "Net-(IC2-EN1)") (class "Default")
      (node (ref "IC2") (pin "1") (pinfunction "EN1_1") (pintype "input"))
      (node (ref "IC2") (pin "11") (pinfunction "EN2_11") (pintype "input"))
      (node (ref "Q4") (pin "3") (pinfunction "C_3") (pintype "passive"))
      (node (ref "R7") (pin "1") (pinfunction "1_1") (pintype "passive"))
    )
    (net (code "33") (name "Net-(IC2-IN1)") (class "Default")
      (node (ref "IC2") (pin "19") (pinfunction "IN4_19") (pintype "input"))
      (node (ref "IC2") (pin "2") (pinfunction "IN1_2") (pintype "input"))
      (node (ref "Q2") (pin "3") (pinfunction "C_3") (pintype "passive"))
      (node (ref "R10") (pin "2") (pinfunction "2_2") (pintype "passive"))
    )
    (net (code "34") (name "Net-(IC2-IN2)") (class "Default")
      (node (ref "IC2") (pin "12") (pinfunction "IN3_12") (pintype "input"))
      (node (ref "IC2") (pin "9") (pinfunction "IN2_9") (pintype "input"))
      (node (ref "Q7") (pin "3") (pinfunction "C_3") (pintype "passive"))
      (node (ref "R4") (pin "1") (pinfunction "1_1") (pintype "passive"))
    )
    (net (code "35") (name "Net-(IC2-OUT1)") (class "Default")
      (node (ref "IC2") (pin "3") (pinfunction "OUT1_3") (pintype "output"))
      (node (ref "MOTOR_L_B") (pin "P1") (pinfunction "1_P1") (pintype "bidirectional"))
    )
    (net (code "36") (name "Net-(IC2-OUT2)") (class "Default")
      (node (ref "IC2") (pin "8") (pinfunction "OUT2_8") (pintype "output"))
      (node (ref "MOTOR_L_B") (pin "P2") (pinfunction "2_P2") (pintype "bidirectional"))
    )
    (net (code "37") (name "Net-(IC2-OUT3)") (class "Default")
      (node (ref "IC2") (pin "13") (pinfunction "OUT3_13") (pintype "output"))
      (node (ref "MOTOR_L_F") (pin "P1") (pinfunction "1_P1") (pintype "bidirectional"))
    )
    (net (code "38") (name "Net-(IC2-OUT4)") (class "Default")
      (node (ref "IC2") (pin "18") (pinfunction "OUT4_18") (pintype "output"))
      (node (ref "MOTOR_L_F") (pin "P2") (pinfunction "2_P2") (pintype "bidirectional"))
    )
    (net (code "39") (name "Net-(IC3-EN1)") (class "Default")
      (node (ref "IC3") (pin "1") (pinfunction "EN1_1") (pintype "input"))
      (node (ref "IC3") (pin "11") (pinfunction "EN2_11") (pintype "input"))
      (node (ref "Q6") (pin "3") (pinfunction "C_3") (pintype "passive"))
      (node (ref "R12") (pin "1") (pinfunction "1_1") (pintype "passive"))
    )
    (net (code "40") (name "Net-(IC3-IN1)") (class "Default")
      (node (ref "IC3") (pin "19") (pinfunction "IN4_19") (pintype "input"))
      (node (ref "IC3") (pin "2") (pinfunction "IN1_2") (pintype "input"))
      (node (ref "Q5") (pin "3") (pinfunction "C_3") (pintype "passive"))
      (node (ref "R14") (pin "2") (pinfunction "2_2") (pintype "passive"))
    )
    (net (code "41") (name "Net-(IC3-IN2)") (class "Default")
      (node (ref "IC3") (pin "12") (pinfunction "IN3_12") (pintype "input"))
      (node (ref "IC3") (pin "9") (pinfunction "IN2_9") (pintype "input"))
      (node (ref "Q8") (pin "3") (pinfunction "C_3") (pintype "passive"))
      (node (ref "R8") (pin "1") (pinfunction "1_1") (pintype "passive"))
    )
    (net (code "42") (name "Net-(IC3-OUT1)") (class "Default")
      (node (ref "IC3") (pin "3") (pinfunction "OUT1_3") (pintype "output"))
      (node (ref "MOTOR_R_B") (pin "P1") (pinfunction "1_P1") (pintype "bidirectional"))
    )
    (net (code "43") (name "Net-(IC3-OUT2)") (class "Default")
      (node (ref "IC3") (pin "8") (pinfunction "OUT2_8") (pintype "output"))
      (node (ref "MOTOR_R_B") (pin "P2") (pinfunction "2_P2") (pintype "bidirectional"))
    )
    (net (code "44") (name "Net-(IC3-OUT3)") (class "Default")
      (node (ref "IC3") (pin "13") (pinfunction "OUT3_13") (pintype "output"))
      (node (ref "MOTOR_R_F") (pin "P1") (pinfunction "1_P1") (pintype "bidirectional"))
    )
    (net (code "45") (name "Net-(IC3-OUT4)") (class "Default")
      (node (ref "IC3") (pin "18") (pinfunction "OUT4_18") (pintype "output"))
      (node (ref "MOTOR_R_F") (pin "P2") (pinfunction "2_P2") (pintype "bidirectional"))
    )
    (net (code "46") (name "Net-(IRLML1-D)") (class "Default")
      (node (ref "D1") (pin "A") (pinfunction "A_A") (pintype "passive"))
      (node (ref "IRLML1") (pin "1") (pinfunction "D_1") (pintype "passive"))
      (node (ref "LIDAR_MOTOR") (pin "P2") (pinfunction "2_P2") (pintype "bidirectional"))
    )
    (net (code "47") (name "Net-(IRLML1-G)") (class "Default")
      (node (ref "IRLML1") (pin "3") (pinfunction "G_3") (pintype "passive"))
      (node (ref "R38") (pin "2") (pinfunction "2_2") (pintype "passive"))
    )
    (net (code "48") (name "Net-(IRLML2502-G)") (class "Default")
      (node (ref "IRLML2502") (pin "3") (pinfunction "G_3") (pintype "passive"))
      (node (ref "R22") (pin "2") (pinfunction "2_2") (pintype "passive"))
    )
    (net (code "49") (name "Net-(KX-9A-2)") (class "Default")
      (node (ref "C37") (pin "2") (pinfunction "2_2") (pintype "passive"))
      (node (ref "KX-9A") (pin "3") (pinfunction "2_3") (pintype "passive"))
      (node (ref "STM32F103CB") (pin "5") (pinfunction "OSC_IN_5") (pintype "bidirectional"))
    )
    (net (code "50") (name "Net-(PCA9533-LED0)") (class "Default")
      (node (ref "PCA9533") (pin "1") (pinfunction "LED0_1") (pintype "bidirectional"))
      (node (ref "R28") (pin "1") (pinfunction "1_1") (pintype "passive"))
    )
    (net (code "51") (name "Net-(PCA9533-LED1)") (class "Default")
      (node (ref "PCA9533") (pin "2") (pinfunction "LED1_2") (pintype "bidirectional"))
      (node (ref "R27") (pin "1") (pinfunction "1_1") (pintype "passive"))
    )
    (net (code "52") (name "Net-(PCA9533-LED2)") (class "Default")
      (node (ref "PCA9533") (pin "3") (pinfunction "LED2_3") (pintype "bidirectional"))
      (node (ref "R26") (pin "1") (pinfunction "1_1") (pintype "passive"))
    )
    (net (code "53") (name "Net-(Q2-B)") (class "Default")
      (node (ref "Q2") (pin "1") (pinfunction "B_1") (pintype "passive"))
      (node (ref "R1") (pin "2") (pinfunction "2_2") (pintype "passive"))
    )
    (net (code "54") (name "Net-(Q4-B)") (class "Default")
      (node (ref "Q4") (pin "1") (pinfunction "B_1") (pintype "passive"))
      (node (ref "R2") (pin "2") (pinfunction "2_2") (pintype "passive"))
    )
    (net (code "55") (name "Net-(Q5-B)") (class "Default")
      (node (ref "Q5") (pin "1") (pinfunction "B_1") (pintype "passive"))
      (node (ref "R5") (pin "2") (pinfunction "2_2") (pintype "passive"))
    )
    (net (code "56") (name "Net-(Q6-B)") (class "Default")
      (node (ref "Q6") (pin "1") (pinfunction "B_1") (pintype "passive"))
      (node (ref "R6") (pin "2") (pinfunction "2_2") (pintype "passive"))
    )
    (net (code "57") (name "Net-(Q7-B)") (class "Default")
      (node (ref "Q7") (pin "1") (pinfunction "B_1") (pintype "passive"))
      (node (ref "R9") (pin "2") (pinfunction "2_2") (pintype "passive"))
    )
    (net (code "58") (name "Net-(Q8-B)") (class "Default")
      (node (ref "Q8") (pin "1") (pinfunction "B_1") (pintype "passive"))
      (node (ref "R13") (pin "2") (pinfunction "2_2") (pintype "passive"))
    )
    (net (code "59") (name "Net-(Q9-B)") (class "Default")
      (node (ref "Q9") (pin "1") (pinfunction "B_1") (pintype "passive"))
      (node (ref "R18") (pin "2") (pinfunction "2_2") (pintype "passive"))
    )
    (net (code "60") (name "Net-(Q9-E)") (class "Default")
      (node (ref "Q9") (pin "2") (pinfunction "E_2") (pintype "passive"))
      (node (ref "R3") (pin "1") (pinfunction "1_1") (pintype "passive"))
    )
    (net (code "61") (name "Net-(R26-Pad2)") (class "Default")
      (node (ref "R26") (pin "2") (pinfunction "2_2") (pintype "passive"))
      (node (ref "RGB_LED") (pin "4") (pinfunction "4_4") (pintype "bidirectional"))
    )
    (net (code "62") (name "Net-(R27-Pad2)") (class "Default")
      (node (ref "R27") (pin "2") (pinfunction "2_2") (pintype "passive"))
      (node (ref "RGB_LED") (pin "3") (pinfunction "3_3") (pintype "bidirectional"))
    )
    (net (code "63") (name "Net-(R28-Pad2)") (class "Default")
      (node (ref "R28") (pin "2") (pinfunction "2_2") (pintype "passive"))
      (node (ref "RGB_LED") (pin "2") (pinfunction "2_2") (pintype "bidirectional"))
    )
    (net (code "64") (name "Net-(STM32F103CB-OSC_OUT)") (class "Default")
      (node (ref "C36") (pin "2") (pinfunction "2_2") (pintype "passive"))
      (node (ref "KX-9A") (pin "1") (pinfunction "1_1") (pintype "passive"))
      (node (ref "STM32F103CB") (pin "6") (pinfunction "OSC_OUT_6") (pintype "bidirectional"))
    )
    (net (code "65") (name "Net-(STM32F103CB-PC13-TAMPER-RTC)") (class "Default")
      (node (ref "R30") (pin "1") (pinfunction "1_1") (pintype "passive"))
      (node (ref "STM32F103CB") (pin "2") (pinfunction "PC13-TAMPER-RTC_2") (pintype "bidirectional"))
    )
    (net (code "66") (name "Net-(U1-CPOUT)") (class "Default")
      (node (ref "C17") (pin "1") (pinfunction "1_1") (pintype "passive"))
      (node (ref "U1") (pin "20") (pinfunction "CPOUT_20") (pintype "passive"))
    )
    (net (code "67") (name "Net-(U1-REGOUT)") (class "Default")
      (node (ref "C21") (pin "1") (pinfunction "1_1") (pintype "passive"))
      (node (ref "U1") (pin "10") (pinfunction "REGOUT_10") (pintype "passive"))
    )
    (net (code "68") (name "V+") (class "Default")
      (node (ref "C16") (pin "1") (pinfunction "1_1") (pintype "passive"))
      (node (ref "C27") (pin "+") (pinfunction "+_+") (pintype "passive"))
      (node (ref "R17") (pin "2") (pinfunction "2_2") (pintype "passive"))
      (node (ref "R34") (pin "2") (pinfunction "2_2") (pintype "passive"))
      (node (ref "SUPPLY_IN") (pin "2") (pinfunction "2_2") (pintype "passive"))
      (node (ref "SUPPLY_IN1") (pin "2") (pinfunction "2_2") (pintype "passive"))
      (node (ref "U2") (pin "1") (pinfunction "VIN+_1") (pintype "bidirectional"))
    )
    (net (code "69") (name "unconnected-(PCA9533-LED3-Pad5)") (class "Default")
      (node (ref "PCA9533") (pin "5") (pinfunction "LED3_5") (pintype "bidirectional"))
    )
    (net (code "70") (name "unconnected-(PI_HEADER-Pad2)") (class "Default")
      (node (ref "PI_HEADER") (pin "2") (pinfunction "2_2") (pintype "passive"))
    )
    (net (code "71") (name "unconnected-(PI_HEADER-Pad3)") (class "Default")
      (node (ref "PI_HEADER") (pin "3") (pinfunction "3_3") (pintype "passive"))
    )
    (net (code "72") (name "unconnected-(PI_HEADER-Pad4)") (class "Default")
      (node (ref "PI_HEADER") (pin "4") (pinfunction "4_4") (pintype "passive"))
    )
    (net (code "73") (name "unconnected-(PI_HEADER-Pad5)") (class "Default")
      (node (ref "PI_HEADER") (pin "5") (pinfunction "5_5") (pintype "passive"))
    )
    (net (code "74") (name "unconnected-(PI_HEADER-Pad6)") (class "Default")
      (node (ref "PI_HEADER") (pin "6") (pinfunction "6_6") (pintype "passive"))
    )
    (net (code "75") (name "unconnected-(PI_HEADER-Pad7)") (class "Default")
      (node (ref "PI_HEADER") (pin "7") (pinfunction "7_7") (pintype "passive"))
    )
    (net (code "76") (name "unconnected-(PI_HEADER-Pad9)") (class "Default")
      (node (ref "PI_HEADER") (pin "9") (pinfunction "9_9") (pintype "passive"))
    )
    (net (code "77") (name "unconnected-(PI_HEADER-Pad10)") (class "Default")
      (node (ref "PI_HEADER") (pin "10") (pinfunction "10_10") (pintype "passive"))
    )
    (net (code "78") (name "unconnected-(PI_HEADER-Pad11)") (class "Default")
      (node (ref "PI_HEADER") (pin "11") (pinfunction "11_11") (pintype "passive"))
    )
    (net (code "79") (name "unconnected-(PI_HEADER-Pad13)") (class "Default")
      (node (ref "PI_HEADER") (pin "13") (pinfunction "13_13") (pintype "passive"))
    )
    (net (code "80") (name "unconnected-(PI_HEADER-Pad14)") (class "Default")
      (node (ref "PI_HEADER") (pin "14") (pinfunction "14_14") (pintype "passive"))
    )
    (net (code "81") (name "unconnected-(PI_HEADER-Pad16)") (class "Default")
      (node (ref "PI_HEADER") (pin "16") (pinfunction "16_16") (pintype "passive"))
    )
    (net (code "82") (name "unconnected-(PI_HEADER-Pad17)") (class "Default")
      (node (ref "PI_HEADER") (pin "17") (pinfunction "17_17") (pintype "passive"))
    )
    (net (code "83") (name "unconnected-(PI_HEADER-Pad18)") (class "Default")
      (node (ref "PI_HEADER") (pin "18") (pinfunction "18_18") (pintype "passive"))
    )
    (net (code "84") (name "unconnected-(PI_HEADER-Pad19)") (class "Default")
      (node (ref "PI_HEADER") (pin "19") (pinfunction "19_19") (pintype "passive"))
    )
    (net (code "85") (name "unconnected-(PI_HEADER-Pad21)") (class "Default")
      (node (ref "PI_HEADER") (pin "21") (pinfunction "21_21") (pintype "passive"))
    )
    (net (code "86") (name "unconnected-(PI_HEADER-Pad23)") (class "Default")
      (node (ref "PI_HEADER") (pin "23") (pinfunction "23_23") (pintype "passive"))
    )
    (net (code "87") (name "unconnected-(PI_HEADER-Pad25)") (class "Default")
      (node (ref "PI_HEADER") (pin "25") (pinfunction "25_25") (pintype "passive"))
    )
    (net (code "88") (name "unconnected-(PI_HEADER-Pad27)") (class "Default")
      (node (ref "PI_HEADER") (pin "27") (pinfunction "27_27") (pintype "passive"))
    )
    (net (code "89") (name "unconnected-(PI_HEADER-Pad29)") (class "Default")
      (node (ref "PI_HEADER") (pin "29") (pinfunction "29_29") (pintype "passive"))
    )
    (net (code "90") (name "unconnected-(PI_HEADER-Pad30)") (class "Default")
      (node (ref "PI_HEADER") (pin "30") (pinfunction "30_30") (pintype "passive"))
    )
    (net (code "91") (name "unconnected-(PI_HEADER-Pad33)") (class "Default")
      (node (ref "PI_HEADER") (pin "33") (pinfunction "33_33") (pintype "passive"))
    )
    (net (code "92") (name "unconnected-(PI_HEADER-Pad35)") (class "Default")
      (node (ref "PI_HEADER") (pin "35") (pinfunction "35_35") (pintype "passive"))
    )
    (net (code "93") (name "unconnected-(PI_HEADER-Pad37)") (class "Default")
      (node (ref "PI_HEADER") (pin "37") (pinfunction "37_37") (pintype "passive"))
    )
    (net (code "94") (name "unconnected-(PI_HEADER-Pad39)") (class "Default")
      (node (ref "PI_HEADER") (pin "39") (pinfunction "39_39") (pintype "passive"))
    )
    (net (code "95") (name "unconnected-(STM32F103CB-PA1-Pad11)") (class "Default")
      (node (ref "STM32F103CB") (pin "11") (pinfunction "PA1_11") (pintype "bidirectional"))
    )
    (net (code "96") (name "unconnected-(STM32F103CB-PA8-Pad29)") (class "Default")
      (node (ref "STM32F103CB") (pin "29") (pinfunction "PA8_29") (pintype "bidirectional"))
    )
    (net (code "97") (name "unconnected-(STM32F103CB-PA15-Pad38)") (class "Default")
      (node (ref "STM32F103CB") (pin "38") (pinfunction "PA15_38") (pintype "bidirectional"))
    )
    (net (code "98") (name "unconnected-(STM32F103CB-PB3-Pad39)") (class "Default")
      (node (ref "STM32F103CB") (pin "39") (pinfunction "PB3_39") (pintype "bidirectional"))
    )
    (net (code "99") (name "unconnected-(STM32F103CB-PB4-Pad40)") (class "Default")
      (node (ref "STM32F103CB") (pin "40") (pinfunction "PB4_40") (pintype "bidirectional"))
    )
    (net (code "100") (name "unconnected-(STM32F103CB-PB5-Pad41)") (class "Default")
      (node (ref "STM32F103CB") (pin "41") (pinfunction "PB5_41") (pintype "bidirectional"))
    )
    (net (code "101") (name "unconnected-(STM32F103CB-PB8-Pad45)") (class "Default")
      (node (ref "STM32F103CB") (pin "45") (pinfunction "PB8_45") (pintype "bidirectional"))
    )
    (net (code "102") (name "unconnected-(STM32F103CB-PB9-Pad46)") (class "Default")
      (node (ref "STM32F103CB") (pin "46") (pinfunction "PB9_46") (pintype "bidirectional"))
    )
    (net (code "103") (name "unconnected-(STM32F103CB-PB10-Pad21)") (class "Default")
      (node (ref "STM32F103CB") (pin "21") (pinfunction "PB10_21") (pintype "bidirectional"))
    )
    (net (code "104") (name "unconnected-(STM32F103CB-PB11-Pad22)") (class "Default")
      (node (ref "STM32F103CB") (pin "22") (pinfunction "PB11_22") (pintype "bidirectional"))
    )
    (net (code "105") (name "unconnected-(STM32F103CB-PB13-Pad26)") (class "Default")
      (node (ref "STM32F103CB") (pin "26") (pinfunction "PB13_26") (pintype "bidirectional"))
    )
    (net (code "106") (name "unconnected-(STM32F103CB-PC14-OSC32_IN-Pad3)") (class "Default")
      (node (ref "STM32F103CB") (pin "3") (pinfunction "PC14-OSC32_IN_3") (pintype "bidirectional"))
    )
    (net (code "107") (name "unconnected-(STM32F103CB-PC15-OSC32_OUT-Pad4)") (class "Default")
      (node (ref "STM32F103CB") (pin "4") (pinfunction "PC15-OSC32_OUT_4") (pintype "bidirectional"))
    )
    (net (code "108") (name "unconnected-(U1-AUX_CL-Pad7)") (class "Default")
      (node (ref "U1") (pin "7") (pinfunction "AUX_CL_7") (pintype "input"))
    )
    (net (code "109") (name "unconnected-(U1-AUX_DA-Pad6)") (class "Default")
      (node (ref "U1") (pin "6") (pinfunction "AUX_DA_6") (pintype "bidirectional"))
    )
    (net (code "110") (name "unconnected-(U1-RESV-Pad19)") (class "Default")
      (node (ref "U1") (pin "19") (pinfunction "RESV_19") (pintype "passive"))
    )
    (net (code "111") (name "unconnected-(U1-RESV-Pad21)") (class "Default")
      (node (ref "U1") (pin "21") (pinfunction "RESV_21") (pintype "passive"))
    )
    (net (code "112") (name "unconnected-(U1-RESV-Pad22)") (class "Default")
      (node (ref "U1") (pin "22") (pinfunction "RESV_22") (pintype "passive"))
    )
  )
)
